# sonar_tx.net
KiCad netlist of a schematic drawn in Altium Designer
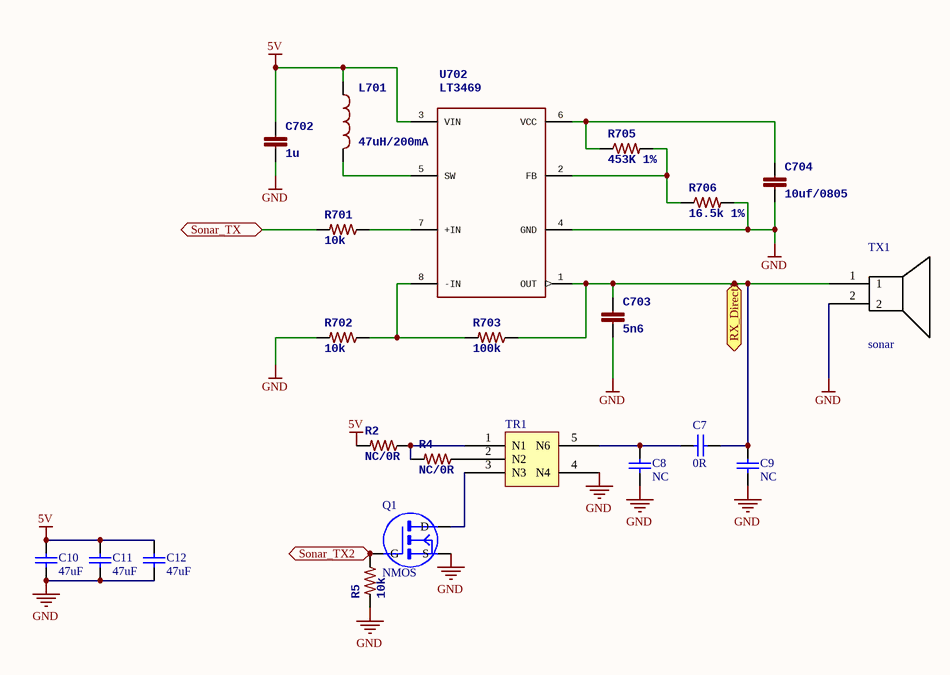
[diagram p0: sonar_tx.SchDoc]

(export (version "E")
  (design (tool "Eeschema 10.0.6"))
  (components
    (comp (ref "C7")
      (value "0R")
      (footprint "0805")
      (description "Capacitor")
      (fields (field (name "Comment") "Cap") (field (name "PUBLISHER") "Altium Limited"))
      (libsource (lib "RTC6705") (part "Cap"))
    )
    (comp (ref "C8")
      (value "NC")
      (footprint "0805")
      (description "Capacitor")
      (fields (field (name "Comment") "Cap") (field (name "PUBLISHER") "Altium Limited"))
      (libsource (lib "RTC6705") (part "Cap"))
    )
    (comp (ref "C9")
      (value "NC")
      (footprint "0805")
      (description "Capacitor")
      (fields (field (name "Comment") "Cap") (field (name "PUBLISHER") "Altium Limited"))
      (libsource (lib "RTC6705") (part "Cap"))
    )
    (comp (ref "C10")
      (value "47uF")
      (footprint "0805")
      (description "Capacitor")
      (fields (field (name "Comment") "Cap") (field (name "PUBLISHER") "Altium Limited"))
      (libsource (lib "RTC6705") (part "Cap"))
    )
    (comp (ref "C11")
      (value "47uF")
      (footprint "0805")
      (description "Capacitor")
      (fields (field (name "Comment") "Cap") (field (name "PUBLISHER") "Altium Limited"))
      (libsource (lib "RTC6705") (part "Cap"))
    )
    (comp (ref "C12")
      (value "47uF")
      (footprint "0805")
      (description "Capacitor")
      (fields (field (name "Comment") "Cap") (field (name "PUBLISHER") "Altium Limited"))
      (libsource (lib "RTC6705") (part "Cap"))
    )
    (comp (ref "C702")
      (value "1u")
      (footprint "0402")
      (description "<b>Capacitor</b>\nStandard 0603 ceramic capacitor, and 0.1\" leaded capacitor.")
      (fields (field (name "PARTNO") "CC0603ZRY5V7BB105"))
      (libsource (lib "pixhawk2") (part "CAP0603"))
    )
    (comp (ref "C703")
      (value "5n6")
      (footprint "0402")
      (description "<b>Capacitor</b>\nStandard 0603 ceramic capacitor, and 0.1\" leaded capacitor.")
      (fields (field (name "PARTNO") "C0402C562K5RACTU"))
      (libsource (lib "pixhawk2") (part "CAP0402"))
    )
    (comp (ref "C704")
      (value "10uf/0805")
      (footprint "0805")
      (description "<b>Capacitor</b>\nStandard 0603 ceramic capacitor, and 0.1\" leaded capacitor.")
      (fields (field (name "PARTNO") "C1005X5R1C474K050BC"))
      (libsource (lib "pixhawk2") (part "CAP0402"))
    )
    (comp (ref "L701")
      (value "47uH/200mA")
      (footprint "0805-IND")
      (fields (field (name "PARTNO") "MLZ2012M470W"))
      (libsource (lib "pixhawk2") (part "INDUCTOR0805"))
    )
    (comp (ref "Q1") (value "NMOS") (footprint "SOT23_L") (libsource (lib "sch") (part "NMOS")))
    (comp (ref "R2")
      (value "NC/0R")
      (footprint "0402")
      (fields (field (name "PARTNO") "RMCF0402FT453K"))
      (libsource (lib "sonar") (part "RESISTOR0402-RES"))
    )
    (comp (ref "R4")
      (value "NC/0R")
      (footprint "0402")
      (fields (field (name "PARTNO") "RMCF0402FT453K"))
      (libsource (lib "sonar") (part "RESISTOR0402-RES"))
    )
    (comp (ref "R5")
      (value "10k")
      (footprint "0402")
      (fields (field (name "PARTNO") "RMCF0402FT453K"))
      (libsource (lib "sonar") (part "RESISTOR0402-RES"))
    )
    (comp (ref "R701")
      (value "10k")
      (footprint "0402")
      (fields (field (name "PARTNO") "RMCF0402FT453K"))
      (libsource (lib "sonar") (part "RESISTOR0402-RES"))
    )
    (comp (ref "R702")
      (value "10k")
      (footprint "0402")
      (fields (field (name "PARTNO") "RMCF0402FT453K"))
      (libsource (lib "sonar") (part "RESISTOR0402-RES"))
    )
    (comp (ref "R703")
      (value "100k")
      (footprint "0402")
      (fields (field (name "PARTNO") "RMCF0402FT453K"))
      (libsource (lib "sonar") (part "RESISTOR0402-RES"))
    )
    (comp (ref "R705")
      (value "453K 1%")
      (footprint "0402")
      (fields (field (name "PARTNO") "RMCF0402FT453K"))
      (libsource (lib "sonar") (part "RESISTOR0402-RES"))
    )
    (comp (ref "R706")
      (value "16.5k 1%")
      (footprint "0402")
      (fields (field (name "PARTNO") "RMCF0402FT453K"))
      (libsource (lib "sonar") (part "RESISTOR0402-RES"))
    )
    (comp (ref "TR1")
      (value "Transformer_B78416A2232A003")
      (footprint "Transformer_B78416A2232A003")
      (libsource (lib "sch") (part "Transformer_B78416A2232A003"))
    )
    (comp (ref "TX1") (value "sonar") (footprint "sonar-16mm") (libsource (lib "schlib") (part "sonar")))
    (comp (ref "U702")
      (value "LT3469")
      (footprint "SOT23-8")
      (description "LT3469 Piezo microactuator driver with boost regulator")
      (fields (field (name "PARTNO") "LT3469ETS8"))
      (libsource (lib "pixhawk2") (part "LT3469"))
    )
  )
  (nets
    (net (code "1") (name "/RX_Direct1") (class "Default")
      (node (ref "C7") (pin "1") (pinfunction "1_1") (pintype "passive"))
      (node (ref "C703") (pin "1") (pinfunction "1_1") (pintype "passive"))
      (node (ref "C9") (pin "1") (pinfunction "1_1") (pintype "passive"))
      (node (ref "R703") (pin "1") (pinfunction "1_1") (pintype "passive"))
      (node (ref "TX1") (pin "1") (pinfunction "1_1") (pintype "passive"))
      (node (ref "U702") (pin "1") (pinfunction "OUT_1") (pintype "output"))
    )
    (net (code "2") (name "/Sonar_TX") (class "Default")
      (node (ref "R701") (pin "2") (pinfunction "2_2") (pintype "passive"))
    )
    (net (code "3") (name "/Sonar_TX2") (class "Default")
      (node (ref "Q1") (pin "G") (pinfunction "G_G") (pintype "passive"))
      (node (ref "R5") (pin "1") (pinfunction "1_1") (pintype "passive"))
    )
    (net (code "4") (name "5V") (class "Default")
      (node (ref "C10") (pin "1") (pinfunction "1_1") (pintype "passive"))
      (node (ref "C11") (pin "1") (pinfunction "1_1") (pintype "passive"))
      (node (ref "C12") (pin "1") (pinfunction "1_1") (pintype "passive"))
      (node (ref "C702") (pin "1") (pinfunction "1_1") (pintype "passive"))
      (node (ref "L701") (pin "1") (pinfunction "1_1") (pintype "passive"))
      (node (ref "R2") (pin "2") (pinfunction "2_2") (pintype "passive"))
      (node (ref "U702") (pin "3") (pinfunction "VIN_3") (pintype "power_in"))
    )
    (net (code "5") (name "GND") (class "Default")
      (node (ref "C10") (pin "2") (pinfunction "2_2") (pintype "passive"))
      (node (ref "C11") (pin "2") (pinfunction "2_2") (pintype "passive"))
      (node (ref "C12") (pin "2") (pinfunction "2_2") (pintype "passive"))
      (node (ref "C702") (pin "2") (pinfunction "2_2") (pintype "passive"))
      (node (ref "C703") (pin "2") (pinfunction "2_2") (pintype "passive"))
      (node (ref "C704") (pin "2") (pinfunction "2_2") (pintype "passive"))
      (node (ref "C8") (pin "2") (pinfunction "2_2") (pintype "passive"))
      (node (ref "C9") (pin "2") (pinfunction "2_2") (pintype "passive"))
      (node (ref "Q1") (pin "S") (pinfunction "S_S") (pintype "passive"))
      (node (ref "R5") (pin "2") (pinfunction "2_2") (pintype "passive"))
      (node (ref "R702") (pin "2") (pinfunction "2_2") (pintype "passive"))
      (node (ref "R706") (pin "2") (pinfunction "2_2") (pintype "passive"))
      (node (ref "TR1") (pin "4") (pinfunction "N4_4") (pintype "passive"))
      (node (ref "TX1") (pin "2") (pinfunction "2_2") (pintype "passive"))
      (node (ref "U702") (pin "4") (pinfunction "GND_4") (pintype "power_in"))
    )
    (net (code "6") (name "Net-(TR1-N1)") (class "Default")
      (node (ref "R2") (pin "1") (pinfunction "1_1") (pintype "passive"))
      (node (ref "R4") (pin "2") (pinfunction "2_2") (pintype "passive"))
      (node (ref "TR1") (pin "1") (pinfunction "N1_1") (pintype "passive"))
    )
    (net (code "7") (name "Net-(TR1-N2)") (class "Default")
      (node (ref "R4") (pin "1") (pinfunction "1_1") (pintype "passive"))
      (node (ref "TR1") (pin "2") (pinfunction "N2_2") (pintype "passive"))
    )
    (net (code "8") (name "Net-(TR1-N3)") (class "Default")
      (node (ref "Q1") (pin "D") (pinfunction "D_D") (pintype "passive"))
      (node (ref "TR1") (pin "3") (pinfunction "N3_3") (pintype "passive"))
    )
    (net (code "9") (name "Net-(TR1-N6)") (class "Default")
      (node (ref "C7") (pin "2") (pinfunction "2_2") (pintype "passive"))
      (node (ref "C8") (pin "1") (pinfunction "1_1") (pintype "passive"))
      (node (ref "TR1") (pin "5") (pinfunction "N6_5") (pintype "passive"))
    )
    (net (code "10") (name "Net-(U702-+IN)") (class "Default")
      (node (ref "R701") (pin "1") (pinfunction "1_1") (pintype "passive"))
      (node (ref "U702") (pin "7") (pinfunction "+IN_7") (pintype "passive"))
    )
    (net (code "11") (name "Net-(U702--IN)") (class "Default")
      (node (ref "R702") (pin "1") (pinfunction "1_1") (pintype "passive"))
      (node (ref "R703") (pin "2") (pinfunction "2_2") (pintype "passive"))
      (node (ref "U702") (pin "8") (pinfunction "-IN_8") (pintype "passive"))
    )
    (net (code "12") (name "Net-(U702-FB)") (class "Default")
      (node (ref "R705") (pin "2") (pinfunction "2_2") (pintype "passive"))
      (node (ref "R706") (pin "1") (pinfunction "1_1") (pintype "passive"))
      (node (ref "U702") (pin "2") (pinfunction "FB_2") (pintype "passive"))
    )
    (net (code "13") (name "Net-(U702-SW)") (class "Default")
      (node (ref "L701") (pin "2") (pinfunction "2_2") (pintype "passive"))
      (node (ref "U702") (pin "5") (pinfunction "SW_5") (pintype "passive"))
    )
    (net (code "14") (name "Net-(U702-VCC)") (class "Default")
      (node (ref "C704") (pin "1") (pinfunction "1_1") (pintype "passive"))
      (node (ref "R705") (pin "1") (pinfunction "1_1") (pintype "passive"))
      (node (ref "U702") (pin "6") (pinfunction "VCC_6") (pintype "passive"))
    )
  )
)
